# ST_LINK_V2-1.net
KiCad netlist of a schematic drawn in Altium Designer
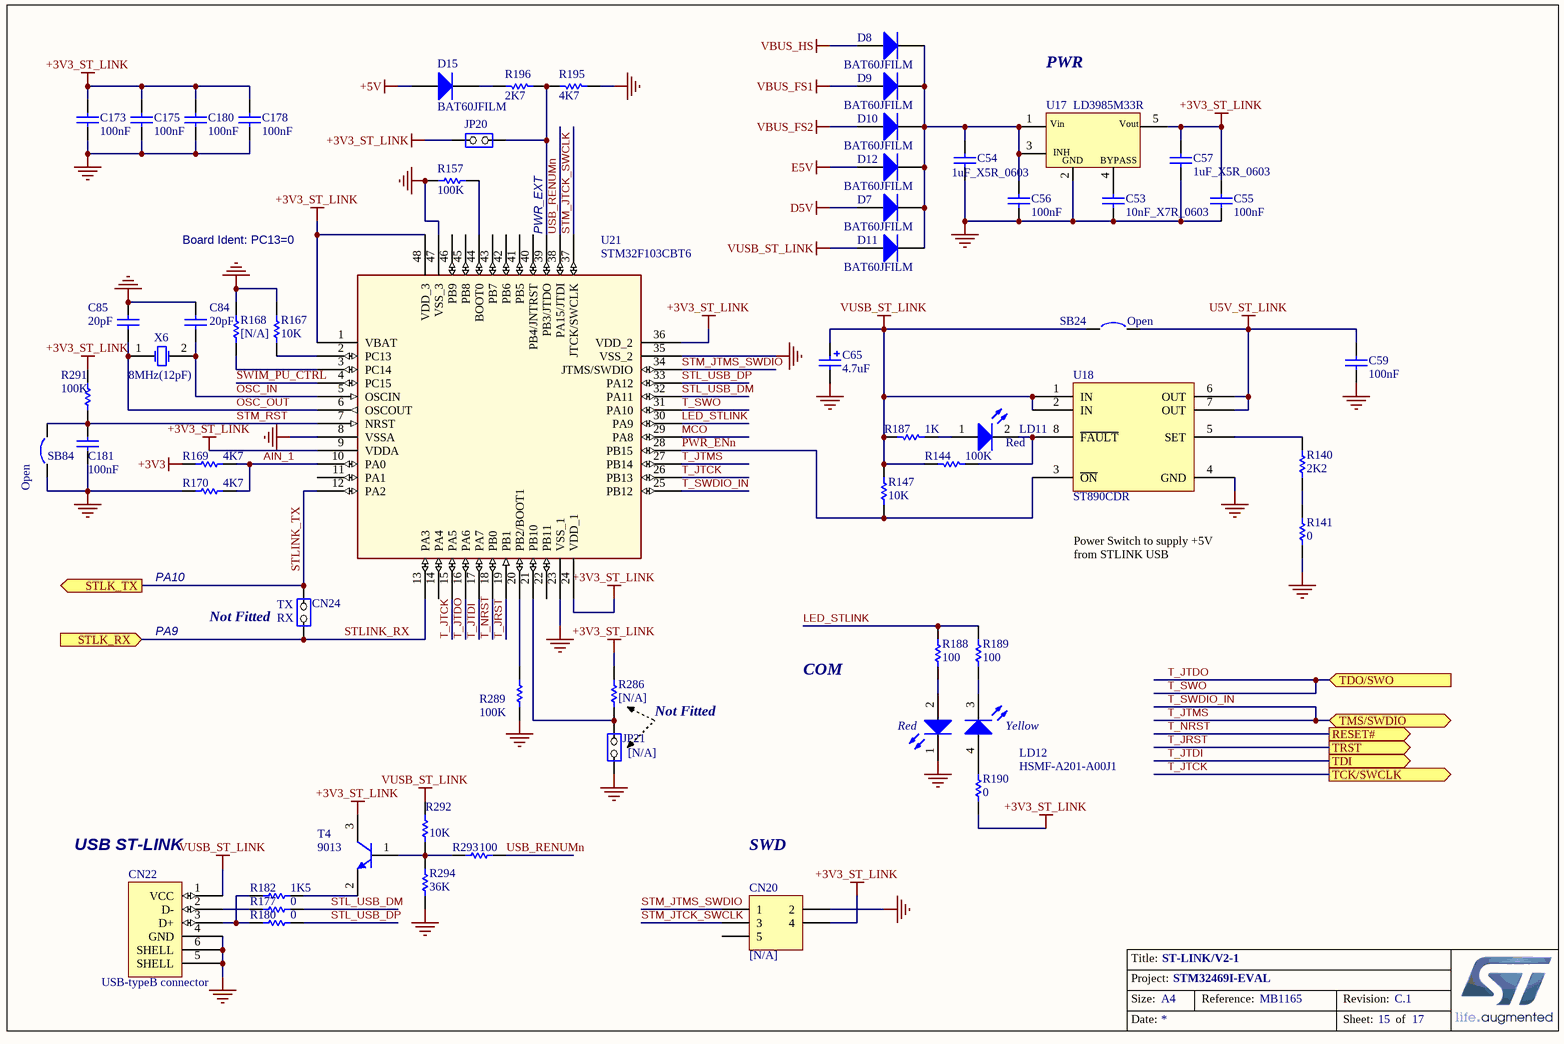
[diagram p0: ST_LINK_V2-1.SCHDOC]

(export (version "E")
  (design (tool "Eeschema 10.0.6"))
  (components
    (comp (ref "C53")
      (value "10nF_X7R_0603")
      (footprint "0603C")
      (description "0603  X7R 10NF")
      (fields (field (name "TOLERANCE") "10%"))
      (libsource (lib "MB963_1") (part "CAP SMD 0603  X7R 10000PF 50V 10%"))
    )
    (comp (ref "C54")
      (value "1uF_X5R_0603")
      (footprint "0603C")
      (description "0603  X5R 1µF")
      (fields (field (name "TOLERANCE") "10%"))
      (libsource (lib "MB963_1") (part "CAP SMD 0603  X5R 1µF 25V 10%"))
    )
    (comp (ref "C55")
      (value "100nF")
      (footprint "0603C")
      (description "Capacitor 0402 / 0603 / 0805")
      (libsource (lib "MCD_TOOLS") (part "Capacitor_ST"))
    )
    (comp (ref "C56")
      (value "100nF")
      (footprint "0603C")
      (description "Capacitor 0402 / 0603 / 0805")
      (libsource (lib "MCD_TOOLS") (part "Capacitor_ST"))
    )
    (comp (ref "C57")
      (value "1uF_X5R_0603")
      (footprint "0603C")
      (description "0603  X5R 1µF")
      (fields (field (name "TOLERANCE") "10%"))
      (libsource (lib "MB963_1") (part "CAP SMD 0603  X5R 1µF 25V 10%"))
    )
    (comp (ref "C59")
      (value "100nF")
      (footprint "0603C")
      (description "Capacitor 0402 / 0603 / 0805")
      (libsource (lib "MCD_TOOLS") (part "Capacitor_ST"))
    )
    (comp (ref "C65")
      (value "4.7uF")
      (footprint "TAN-A")
      (description "Polarized Capacitor (Radial)")
      (fields (field (name "PUBLISHER") "Altium Limited"))
      (libsource (lib "*") (part "Cap Pol1"))
    )
    (comp (ref "C84")
      (value "20pF")
      (footprint "0603C")
      (description "Capacitor 0402 / 0603 / 0805")
      (libsource (lib "MCD_TOOLS") (part "Capacitor_ST"))
    )
    (comp (ref "C85")
      (value "20pF")
      (footprint "0603C")
      (description "Capacitor 0402 / 0603 / 0805")
      (libsource (lib "MCD_TOOLS") (part "Capacitor_ST"))
    )
    (comp (ref "C173")
      (value "100nF")
      (footprint "0603C")
      (description "Capacitor 0402 / 0603 / 0805")
      (libsource (lib "MCD_TOOLS") (part "Capacitor_ST"))
    )
    (comp (ref "C175")
      (value "100nF")
      (footprint "0603C")
      (description "Capacitor 0402 / 0603 / 0805")
      (libsource (lib "MCD_TOOLS") (part "Capacitor_ST"))
    )
    (comp (ref "C178")
      (value "100nF")
      (footprint "0603C")
      (description "Capacitor 0402 / 0603 / 0805")
      (libsource (lib "MCD_TOOLS") (part "Capacitor_ST"))
    )
    (comp (ref "C180")
      (value "100nF")
      (footprint "0603C")
      (description "Capacitor 0402 / 0603 / 0805")
      (libsource (lib "MCD_TOOLS") (part "Capacitor_ST"))
    )
    (comp (ref "C181")
      (value "100nF")
      (footprint "0603C")
      (description "Capacitor 0402 / 0603 / 0805")
      (libsource (lib "MCD_TOOLS") (part "Capacitor_ST"))
    )
    (comp (ref "CN20")
      (value "[N/A]")
      (footprint "HDR_2X3-1_2R54-6")
      (description "Header, 3-Pin, Dual row")
      (fields (field (name "PUBLISHER") "Altium Limited"))
      (libsource (lib "Miscellaneous Connectors") (part "Header 3X2"))
    )
    (comp (ref "CN22")
      (value "USB-typeB connector")
      (footprint "USB-B")
      (libsource (lib "mb1045") (part "USB-typeB connector"))
    )
    (comp (ref "CN24") (value "~") (footprint "SIP2") (libsource (lib "MCD_TOOLS") (part "JP2")))
    (comp (ref "D7")
      (value "BAT60JFILM")
      (footprint "SOD-323")
      (libsource (lib "MCD_TOOLS") (part "BAT60JFILM"))
    )
    (comp (ref "D8")
      (value "BAT60JFILM")
      (footprint "SOD-323")
      (libsource (lib "MCD_TOOLS") (part "BAT60JFILM"))
    )
    (comp (ref "D9")
      (value "BAT60JFILM")
      (footprint "SOD-323")
      (libsource (lib "MCD_TOOLS") (part "BAT60JFILM"))
    )
    (comp (ref "D10")
      (value "BAT60JFILM")
      (footprint "SOD-323")
      (libsource (lib "MCD_TOOLS") (part "BAT60JFILM"))
    )
    (comp (ref "D11")
      (value "BAT60JFILM")
      (footprint "SOD-323")
      (libsource (lib "MCD_TOOLS") (part "BAT60JFILM"))
    )
    (comp (ref "D12")
      (value "BAT60JFILM")
      (footprint "SOD-323")
      (libsource (lib "MCD_TOOLS") (part "BAT60JFILM"))
    )
    (comp (ref "D15")
      (value "BAT60JFILM")
      (footprint "SOD-323")
      (description "Default Diode")
      (fields (field (name "PUBLISHER") "Altium Limited"))
      (libsource (lib "MB1144_1") (part "Diode"))
    )
    (comp (ref "JP20") (value "~") (footprint "SIP2") (libsource (lib "*") (part "JP2")))
    (comp (ref "JP21") (value "[N/A]") (footprint "SIP2") (libsource (lib "*") (part "JP2")))
    (comp (ref "LD11")
      (value "Red")
      (footprint "0603D")
      (description "Typical RED, GREEN, YELLOW, AMBER GaAs LED")
      (fields (field (name "PUBLISHER") "Altium Limited"))
      (libsource (lib "Miscellaneous Devices") (part "LED2"))
    )
    (comp (ref "LD12")
      (value "HSMF-A201-A00J1")
      (footprint "LED2_3528")
      (libsource (lib "MB819") (part "HSMF-A201-A00J1"))
    )
    (comp (ref "R140")
      (value "2K2")
      (footprint "0402R")
      (description "Resistor 0402 or 0603 or 0805")
      (libsource (lib "MCD_TOOLS") (part "Resistor_ST"))
    )
    (comp (ref "R141")
      (value "0")
      (footprint "0603R")
      (description "Resistor")
      (fields (field (name "PUBLISHER") "Altium Limited"))
      (libsource (lib "") (part "Res1_1"))
    )
    (comp (ref "R144")
      (value "100K")
      (footprint "0603R")
      (description "Resistor")
      (fields (field (name "PUBLISHER") "Altium Limited"))
      (libsource (lib "*") (part "Res1"))
    )
    (comp (ref "R147")
      (value "10K")
      (footprint "0402R")
      (description "Resistor 0402 or 0603 or 0805")
      (libsource (lib "MCD_TOOLS") (part "Resistor_ST"))
    )
    (comp (ref "R157")
      (value "100K")
      (footprint "0603R")
      (description "Resistor 0402 or 0603 or 0805")
      (libsource (lib "Miscellaneous Devices") (part "Res1"))
    )
    (comp (ref "R167")
      (value "10K")
      (footprint "0603R")
      (description "Resistor 0402 or 0603 or 0805")
      (libsource (lib "Miscellaneous Devices") (part "Res1"))
    )
    (comp (ref "R168")
      (value "[N/A]")
      (footprint "0603R")
      (description "Resistor 0402 or 0603 or 0805")
      (libsource (lib "Miscellaneous Devices") (part "Res1"))
    )
    (comp (ref "R169")
      (value "4K7")
      (footprint "0603R")
      (description "Resistor 0402 or 0603 or 0805")
      (libsource (lib "Miscellaneous Devices") (part "Res1"))
    )
    (comp (ref "R170")
      (value "4K7")
      (footprint "0603R")
      (description "Resistor 0402 or 0603 or 0805")
      (libsource (lib "Miscellaneous Devices") (part "Res1"))
    )
    (comp (ref "R177")
      (value "0")
      (footprint "0603R")
      (description "Resistor 0402 or 0603 or 0805")
      (libsource (lib "Miscellaneous Devices") (part "Res1"))
    )
    (comp (ref "R180")
      (value "0")
      (footprint "0603R")
      (description "Resistor 0402 or 0603 or 0805")
      (libsource (lib "Miscellaneous Devices") (part "Res1"))
    )
    (comp (ref "R182")
      (value "1K5")
      (footprint "0603R")
      (description "Resistor 0402 or 0603 or 0805")
      (libsource (lib "Miscellaneous Devices") (part "Res1"))
    )
    (comp (ref "R187")
      (value "1K")
      (footprint "0603R")
      (description "Resistor")
      (fields (field (name "PUBLISHER") "Altium Limited"))
      (libsource (lib "*") (part "Res1"))
    )
    (comp (ref "R188")
      (value "100")
      (footprint "0603R")
      (description "Resistor")
      (fields (field (name "PUBLISHER") "Altium Limited"))
      (libsource (lib "") (part "Res1_1"))
    )
    (comp (ref "R189")
      (value "100")
      (footprint "0603R")
      (description "Resistor")
      (fields (field (name "PUBLISHER") "Altium Limited"))
      (libsource (lib "") (part "Res1_1"))
    )
    (comp (ref "R190")
      (value "0")
      (footprint "0603R")
      (description "Resistor")
      (fields (field (name "PUBLISHER") "Altium Limited"))
      (libsource (lib "") (part "Res1_1"))
    )
    (comp (ref "R195")
      (value "4K7")
      (footprint "0603R")
      (description "Resistor")
      (fields (field (name "PUBLISHER") "Altium Limited"))
      (libsource (lib "") (part "Res1_2"))
    )
    (comp (ref "R196")
      (value "2K7")
      (footprint "0603R")
      (description "Resistor")
      (fields (field (name "PUBLISHER") "Altium Limited"))
      (libsource (lib "") (part "Res1_2"))
    )
    (comp (ref "R286")
      (value "[N/A]")
      (footprint "0603R")
      (description "Resistor")
      (fields (field (name "PUBLISHER") "Altium Limited"))
      (libsource (lib "") (part "Res1_1"))
    )
    (comp (ref "R289")
      (value "100K")
      (footprint "0603R")
      (description "Resistor 0402 or 0603 or 0805")
      (libsource (lib "Miscellaneous Devices") (part "Res1"))
    )
    (comp (ref "R291")
      (value "100K")
      (footprint "0603R")
      (description "Resistor 0402 or 0603 or 0805")
      (libsource (lib "Miscellaneous Devices") (part "Res1"))
    )
    (comp (ref "R292")
      (value "10K")
      (footprint "0603R")
      (description "Resistor")
      (fields (field (name "PUBLISHER") "Altium Limited"))
      (libsource (lib "") (part "Res1_1"))
    )
    (comp (ref "R293")
      (value "100")
      (footprint "0603R")
      (description "Resistor 0402 or 0603 or 0805")
      (libsource (lib "Miscellaneous Devices") (part "Res1"))
    )
    (comp (ref "R294")
      (value "36K")
      (footprint "0603R")
      (description "Resistor")
      (fields (field (name "PUBLISHER") "Altium Limited"))
      (libsource (lib "") (part "Res1_1"))
    )
    (comp (ref "SB24")
      (value "Open")
      (footprint "SB_0603")
      (description "Circuit Breaker")
      (fields (field (name "PUBLISHER") "Altium Limited"))
      (libsource (lib "MB1165") (part "Circuit Breaker"))
    )
    (comp (ref "SB84")
      (value "Open")
      (footprint "SB_0603")
      (description "Circuit Breaker")
      (fields (field (name "PUBLISHER") "Altium Limited"))
      (libsource (lib "MB1165") (part "Circuit Breaker"))
    )
    (comp (ref "T4")
      (value "9013")
      (footprint "SOT-23")
      (description "NPN Bipolar Transistor")
      (fields (field (name "PUBLISHER") "Altium Limited"))
      (libsource (lib "MB1167") (part "NPN"))
    )
    (comp (ref "U17")
      (value "LD3985M33R")
      (footprint "SOT23-5")
      (description "Ultra low drop-low noise BiCMOS voltage, regulators low ESR capacitors compatible")
      (libsource (lib "MCD_TOOLS") (part "LD3985M33R"))
    )
    (comp (ref "U18")
      (value "ST890CDR")
      (footprint "SOIC8_1R27_4R9X6")
      (libsource (lib "MB1167") (part "ST890CDR"))
    )
    (comp (ref "U21")
      (value "STM32F103CBT6")
      (footprint "LQFP48_0R5_9X9")
      (description "Medium-density performance line ARM-based 32-bit MCU with 64KB Flash")
      (libsource (lib "Nucleo_64") (part "STM32F103CBT6"))
    )
    (comp (ref "X6")
      (value "8MHz(12pF)")
      (footprint "XTAL_2SM_12R7X4R7")
      (description "Crystal Oscillator")
      (fields (field (name "PUBLISHER") "Altium Limited"))
      (libsource (lib "MB963_1") (part "XTAL"))
    )
  )
  (nets
    (net (code "1") (name "+3V3") (class "Default")
      (node (ref "R169") (pin "1") (pinfunction "1_1") (pintype "passive"))
    )
    (net (code "2") (name "+3V3_ST_LINK") (class "Default")
      (node (ref "C173") (pin "2") (pinfunction "2_2") (pintype "passive"))
      (node (ref "C175") (pin "2") (pinfunction "2_2") (pintype "passive"))
      (node (ref "C178") (pin "2") (pinfunction "2_2") (pintype "passive"))
      (node (ref "C180") (pin "2") (pinfunction "2_2") (pintype "passive"))
      (node (ref "C55") (pin "2") (pinfunction "2_2") (pintype "passive"))
      (node (ref "C57") (pin "1") (pinfunction "1_1") (pintype "passive"))
      (node (ref "CN20") (pin "4") (pinfunction "4_4") (pintype "passive"))
      (node (ref "JP20") (pin "1") (pinfunction "COMMON_1") (pintype "passive"))
      (node (ref "R190") (pin "2") (pinfunction "2_2") (pintype "passive"))
      (node (ref "R286") (pin "1") (pinfunction "1_1") (pintype "passive"))
      (node (ref "R291") (pin "2") (pinfunction "2_2") (pintype "passive"))
      (node (ref "T4") (pin "3") (pinfunction "C_3") (pintype "passive"))
      (node (ref "U17") (pin "5") (pinfunction "Vout_5") (pintype "passive"))
      (node (ref "U21") (pin "1") (pinfunction "VBAT_1") (pintype "power_in"))
      (node (ref "U21") (pin "24") (pinfunction "VDD_1_24") (pintype "power_in"))
      (node (ref "U21") (pin "36") (pinfunction "VDD_2_36") (pintype "power_in"))
      (node (ref "U21") (pin "48") (pinfunction "VDD_3_48") (pintype "power_in"))
      (node (ref "U21") (pin "9") (pinfunction "VDDA_9") (pintype "power_in"))
    )
    (net (code "3") (name "+5V") (class "Default")
      (node (ref "D15") (pin "1") (pinfunction "A_1") (pintype "passive"))
    )
    (net (code "4") (name "/AIN_1") (class "Default")
      (node (ref "R169") (pin "2") (pinfunction "2_2") (pintype "passive"))
      (node (ref "R170") (pin "2") (pinfunction "2_2") (pintype "passive"))
      (node (ref "U21") (pin "10") (pinfunction "PA0_10") (pintype "bidirectional"))
    )
    (net (code "5") (name "/LED_STLINK") (class "Default")
      (node (ref "R188") (pin "1") (pinfunction "1_1") (pintype "passive"))
      (node (ref "R189") (pin "1") (pinfunction "1_1") (pintype "passive"))
      (node (ref "U21") (pin "30") (pinfunction "PA9_30") (pintype "bidirectional"))
    )
    (net (code "6") (name "/MCO") (class "Default")
      (node (ref "U21") (pin "29") (pinfunction "PA8_29") (pintype "bidirectional"))
    )
    (net (code "7") (name "/OSC_IN") (class "Default")
      (node (ref "C84") (pin "1") (pinfunction "1_1") (pintype "passive"))
      (node (ref "U21") (pin "5") (pinfunction "OSCIN_5") (pintype "input"))
      (node (ref "X6") (pin "2") (pinfunction "OSC2_2") (pintype "passive"))
    )
    (net (code "8") (name "/OSC_OUT") (class "Default")
      (node (ref "C85") (pin "1") (pinfunction "1_1") (pintype "passive"))
      (node (ref "U21") (pin "6") (pinfunction "OSCOUT_6") (pintype "output"))
      (node (ref "X6") (pin "1") (pinfunction "OSC1_1") (pintype "passive"))
    )
    (net (code "9") (name "/PWR_ENn") (class "Default")
      (node (ref "R147") (pin "2") (pinfunction "2_2") (pintype "passive"))
      (node (ref "U18") (pin "3") (pinfunction "~{ON}_3") (pintype "passive"))
      (node (ref "U21") (pin "28") (pinfunction "PB15_28") (pintype "bidirectional"))
    )
    (net (code "10") (name "/STLINK_RX") (class "Default")
      (node (ref "CN24") (pin "1") (pinfunction "COMMON_1") (pintype "passive"))
      (node (ref "U21") (pin "13") (pinfunction "PA3_13") (pintype "bidirectional"))
    )
    (net (code "11") (name "/STLINK_TX") (class "Default")
      (node (ref "CN24") (pin "2") (pinfunction "NO_2") (pintype "passive"))
      (node (ref "U21") (pin "12") (pinfunction "PA2_12") (pintype "bidirectional"))
    )
    (net (code "12") (name "/STL_USB_DM") (class "Default")
      (node (ref "R177") (pin "2") (pinfunction "2_2") (pintype "passive"))
      (node (ref "U21") (pin "32") (pinfunction "PA11_32") (pintype "bidirectional"))
    )
    (net (code "13") (name "/STL_USB_DP") (class "Default")
      (node (ref "R180") (pin "2") (pinfunction "2_2") (pintype "passive"))
      (node (ref "U21") (pin "33") (pinfunction "PA12_33") (pintype "bidirectional"))
    )
    (net (code "14") (name "/STM_JTCK_SWCLK") (class "Default")
      (node (ref "CN20") (pin "3") (pinfunction "3_3") (pintype "passive"))
      (node (ref "U21") (pin "37") (pinfunction "JTCK/SWCLK_37") (pintype "bidirectional"))
    )
    (net (code "15") (name "/STM_JTMS_SWDIO") (class "Default")
      (node (ref "CN20") (pin "1") (pinfunction "1_1") (pintype "passive"))
      (node (ref "U21") (pin "34") (pinfunction "JTMS/SWDIO_34") (pintype "bidirectional"))
    )
    (net (code "16") (name "/STM_RST") (class "Default")
      (node (ref "C181") (pin "2") (pinfunction "2_2") (pintype "passive"))
      (node (ref "R291") (pin "1") (pinfunction "1_1") (pintype "passive"))
      (node (ref "SB84") (pin "2") (pinfunction "2_2") (pintype "passive"))
      (node (ref "U21") (pin "7") (pinfunction "NRST_7") (pintype "input"))
    )
    (net (code "17") (name "/SWIM_PU_CTRL") (class "Default")
      (node (ref "U21") (pin "4") (pinfunction "PC15_4") (pintype "bidirectional"))
    )
    (net (code "18") (name "/T_JRST") (class "Default")
      (node (ref "U21") (pin "19") (pinfunction "PB1_19") (pintype "input"))
    )
    (net (code "19") (name "/T_JTCK") (class "Default")
      (node (ref "U21") (pin "15") (pinfunction "PA5_15") (pintype "bidirectional"))
      (node (ref "U21") (pin "26") (pinfunction "PB13_26") (pintype "bidirectional"))
    )
    (net (code "20") (name "/T_JTDI") (class "Default")
      (node (ref "U21") (pin "17") (pinfunction "PA7_17") (pintype "bidirectional"))
    )
    (net (code "21") (name "/T_JTDO") (class "Default")
      (node (ref "U21") (pin "16") (pinfunction "PA6_16") (pintype "bidirectional"))
      (node (ref "U21") (pin "31") (pinfunction "PA10_31") (pintype "bidirectional"))
    )
    (net (code "22") (name "/T_JTMS") (class "Default")
      (node (ref "U21") (pin "25") (pinfunction "PB12_25") (pintype "bidirectional"))
      (node (ref "U21") (pin "27") (pinfunction "PB14_27") (pintype "bidirectional"))
    )
    (net (code "23") (name "/T_NRST") (class "Default")
      (node (ref "U21") (pin "18") (pinfunction "PB0_18") (pintype "bidirectional"))
    )
    (net (code "24") (name "/USB_RENUMn") (class "Default")
      (node (ref "R293") (pin "2") (pinfunction "2_2") (pintype "passive"))
      (node (ref "U21") (pin "38") (pinfunction "PA15/JTDI_38") (pintype "bidirectional"))
    )
    (net (code "25") (name "D5V") (class "Default")
      (node (ref "D7") (pin "1") (pinfunction "A_1") (pintype "passive"))
    )
    (net (code "26") (name "E5V") (class "Default")
      (node (ref "D12") (pin "1") (pinfunction "A_1") (pintype "passive"))
    )
    (net (code "27") (name "GND") (class "Default")
      (node (ref "C173") (pin "1") (pinfunction "1_1") (pintype "passive"))
      (node (ref "C175") (pin "1") (pinfunction "1_1") (pintype "passive"))
      (node (ref "C178") (pin "1") (pinfunction "1_1") (pintype "passive"))
      (node (ref "C180") (pin "1") (pinfunction "1_1") (pintype "passive"))
      (node (ref "C181") (pin "1") (pinfunction "1_1") (pintype "passive"))
      (node (ref "C53") (pin "1") (pinfunction "1_1") (pintype "passive"))
      (node (ref "C54") (pin "1") (pinfunction "1_1") (pintype "passive"))
      (node (ref "C55") (pin "1") (pinfunction "1_1") (pintype "passive"))
      (node (ref "C56") (pin "1") (pinfunction "1_1") (pintype "passive"))
      (node (ref "C57") (pin "2") (pinfunction "2_2") (pintype "passive"))
      (node (ref "C59") (pin "1") (pinfunction "1_1") (pintype "passive"))
      (node (ref "C65") (pin "2") (pinfunction "2_2") (pintype "passive"))
      (node (ref "C84") (pin "2") (pinfunction "2_2") (pintype "passive"))
      (node (ref "C85") (pin "2") (pinfunction "2_2") (pintype "passive"))
      (node (ref "CN20") (pin "2") (pinfunction "2_2") (pintype "passive"))
      (node (ref "CN22") (pin "4") (pinfunction "GND_4") (pintype "passive"))
      (node (ref "CN22") (pin "5") (pinfunction "SHELL_5") (pintype "power_in"))
      (node (ref "CN22") (pin "6") (pinfunction "SHELL_6") (pintype "power_in"))
      (node (ref "JP21") (pin "1") (pinfunction "COMMON_1") (pintype "passive"))
      (node (ref "LD12") (pin "1") (pinfunction "RED_cathode_1") (pintype "passive"))
      (node (ref "R141") (pin "1") (pinfunction "1_1") (pintype "passive"))
      (node (ref "R157") (pin "1") (pinfunction "1_1") (pintype "passive"))
      (node (ref "R167") (pin "1") (pinfunction "1_1") (pintype "passive"))
      (node (ref "R168") (pin "1") (pinfunction "1_1") (pintype "passive"))
      (node (ref "R170") (pin "1") (pinfunction "1_1") (pintype "passive"))
      (node (ref "R195") (pin "2") (pinfunction "2_2") (pintype "passive"))
      (node (ref "R289") (pin "1") (pinfunction "1_1") (pintype "passive"))
      (node (ref "R294") (pin "1") (pinfunction "1_1") (pintype "passive"))
      (node (ref "SB84") (pin "1") (pinfunction "1_1") (pintype "passive"))
      (node (ref "U17") (pin "2") (pinfunction "GND_2") (pintype "passive"))
      (node (ref "U18") (pin "4") (pinfunction "GND_4") (pintype "passive"))
      (node (ref "U21") (pin "23") (pinfunction "VSS_1_23") (pintype "power_in"))
      (node (ref "U21") (pin "35") (pinfunction "VSS_2_35") (pintype "power_in"))
      (node (ref "U21") (pin "47") (pinfunction "VSS_3_47") (pintype "power_in"))
      (node (ref "U21") (pin "8") (pinfunction "VSSA_8") (pintype "power_in"))
    )
    (net (code "28") (name "Net-(CN22-D+)") (class "Default")
      (node (ref "CN22") (pin "3") (pinfunction "D+_3") (pintype "bidirectional"))
      (node (ref "R180") (pin "1") (pinfunction "1_1") (pintype "passive"))
      (node (ref "R182") (pin "1") (pinfunction "1_1") (pintype "passive"))
    )
    (net (code "29") (name "Net-(CN22-D-)") (class "Default")
      (node (ref "CN22") (pin "2") (pinfunction "D-_2") (pintype "bidirectional"))
      (node (ref "R177") (pin "1") (pinfunction "1_1") (pintype "passive"))
    )
    (net (code "30") (name "Net-(D10-K)") (class "Default")
      (node (ref "C54") (pin "2") (pinfunction "2_2") (pintype "passive"))
      (node (ref "C56") (pin "2") (pinfunction "2_2") (pintype "passive"))
      (node (ref "D10") (pin "2") (pinfunction "K_2") (pintype "passive"))
      (node (ref "D11") (pin "2") (pinfunction "K_2") (pintype "passive"))
      (node (ref "D12") (pin "2") (pinfunction "K_2") (pintype "passive"))
      (node (ref "D7") (pin "2") (pinfunction "K_2") (pintype "passive"))
      (node (ref "D8") (pin "2") (pinfunction "K_2") (pintype "passive"))
      (node (ref "D9") (pin "2") (pinfunction "K_2") (pintype "passive"))
      (node (ref "U17") (pin "1") (pinfunction "Vin_1") (pintype "passive"))
      (node (ref "U17") (pin "3") (pinfunction "CE_3") (pintype "passive"))
    )
    (net (code "31") (name "Net-(D15-K)") (class "Default")
      (node (ref "D15") (pin "2") (pinfunction "K_2") (pintype "passive"))
      (node (ref "R196") (pin "1") (pinfunction "1_1") (pintype "passive"))
    )
    (net (code "32") (name "Net-(JP20-NO)") (class "Default")
      (node (ref "JP20") (pin "2") (pinfunction "NO_2") (pintype "passive"))
      (node (ref "R195") (pin "1") (pinfunction "1_1") (pintype "passive"))
      (node (ref "R196") (pin "2") (pinfunction "2_2") (pintype "passive"))
      (node (ref "U21") (pin "39") (pinfunction "PB3/JTDO_39") (pintype "bidirectional"))
    )
    (net (code "33") (name "Net-(JP21-NO)") (class "Default")
      (node (ref "JP21") (pin "2") (pinfunction "NO_2") (pintype "passive"))
      (node (ref "R286") (pin "2") (pinfunction "2_2") (pintype "passive"))
      (node (ref "U21") (pin "21") (pinfunction "PB10_21") (pintype "bidirectional"))
    )
    (net (code "34") (name "Net-(LD11-A)") (class "Default")
      (node (ref "LD11") (pin "1") (pinfunction "A_1") (pintype "passive"))
      (node (ref "R187") (pin "2") (pinfunction "2_2") (pintype "passive"))
    )
    (net (code "35") (name "Net-(LD11-K)") (class "Default")
      (node (ref "LD11") (pin "2") (pinfunction "K_2") (pintype "passive"))
      (node (ref "R144") (pin "2") (pinfunction "2_2") (pintype "passive"))
      (node (ref "U18") (pin "8") (pinfunction "~{FAULT}_8") (pintype "passive"))
    )
    (net (code "36") (name "Net-(LD12-Red_anode)") (class "Default")
      (node (ref "LD12") (pin "2") (pinfunction "Red_anode_2") (pintype "passive"))
      (node (ref "R188") (pin "2") (pinfunction "2_2") (pintype "passive"))
    )
    (net (code "37") (name "Net-(LD12-YellowGreen_anode)") (class "Default")
      (node (ref "LD12") (pin "4") (pinfunction "YellowGreen_anode_4") (pintype "passive"))
      (node (ref "R190") (pin "1") (pinfunction "1_1") (pintype "passive"))
    )
    (net (code "38") (name "Net-(LD12-YellowGreen_cathode)") (class "Default")
      (node (ref "LD12") (pin "3") (pinfunction "YellowGreen_cathode_3") (pintype "passive"))
      (node (ref "R189") (pin "2") (pinfunction "2_2") (pintype "passive"))
    )
    (net (code "39") (name "Net-(R140-Pad1)") (class "Default")
      (node (ref "R140") (pin "1") (pinfunction "1_1") (pintype "passive"))
      (node (ref "R141") (pin "2") (pinfunction "2_2") (pintype "passive"))
    )
    (net (code "40") (name "Net-(T4-B)") (class "Default")
      (node (ref "R292") (pin "1") (pinfunction "1_1") (pintype "passive"))
      (node (ref "R293") (pin "1") (pinfunction "1_1") (pintype "passive"))
      (node (ref "R294") (pin "2") (pinfunction "2_2") (pintype "passive"))
      (node (ref "T4") (pin "1") (pinfunction "B_1") (pintype "passive"))
    )
    (net (code "41") (name "Net-(T4-E)") (class "Default")
      (node (ref "R182") (pin "2") (pinfunction "2_2") (pintype "passive"))
      (node (ref "T4") (pin "2") (pinfunction "E_2") (pintype "passive"))
    )
    (net (code "42") (name "Net-(U17-BYPASS)") (class "Default")
      (node (ref "C53") (pin "2") (pinfunction "2_2") (pintype "passive"))
      (node (ref "U17") (pin "4") (pinfunction "BYPASS_4") (pintype "passive"))
    )
    (net (code "43") (name "Net-(U18-SET)") (class "Default")
      (node (ref "R140") (pin "2") (pinfunction "2_2") (pintype "passive"))
      (node (ref "U18") (pin "5") (pinfunction "SET_5") (pintype "passive"))
    )
    (net (code "44") (name "Net-(U21-BOOT0)") (class "Default")
      (node (ref "R157") (pin "2") (pinfunction "2_2") (pintype "passive"))
      (node (ref "U21") (pin "44") (pinfunction "BOOT0_44") (pintype "bidirectional"))
    )
    (net (code "45") (name "Net-(U21-PB2{slash}BOOT1)") (class "Default")
      (node (ref "R289") (pin "2") (pinfunction "2_2") (pintype "passive"))
      (node (ref "U21") (pin "20") (pinfunction "PB2/BOOT1_20") (pintype "bidirectional"))
    )
    (net (code "46") (name "Net-(U21-PC13)") (class "Default")
      (node (ref "R167") (pin "2") (pinfunction "2_2") (pintype "passive"))
      (node (ref "U21") (pin "2") (pinfunction "PC13_2") (pintype "bidirectional"))
    )
    (net (code "47") (name "Net-(U21-PC14)") (class "Default")
      (node (ref "R168") (pin "2") (pinfunction "2_2") (pintype "passive"))
      (node (ref "U21") (pin "3") (pinfunction "PC14_3") (pintype "bidirectional"))
    )
    (net (code "48") (name "U5V_ST_LINK") (class "Default")
      (node (ref "C59") (pin "2") (pinfunction "2_2") (pintype "passive"))
      (node (ref "SB24") (pin "2") (pinfunction "2_2") (pintype "passive"))
      (node (ref "U18") (pin "6") (pinfunction "OUT_6") (pintype "passive"))
      (node (ref "U18") (pin "7") (pinfunction "OUT_7") (pintype "passive"))
    )
    (net (code "49") (name "VBUS_FS1") (class "Default")
      (node (ref "D9") (pin "1") (pinfunction "A_1") (pintype "passive"))
    )
    (net (code "50") (name "VBUS_FS2") (class "Default")
      (node (ref "D10") (pin "1") (pinfunction "A_1") (pintype "passive"))
    )
    (net (code "51") (name "VBUS_HS") (class "Default")
      (node (ref "D8") (pin "1") (pinfunction "A_1") (pintype "passive"))
    )
    (net (code "52") (name "VUSB_ST_LINK") (class "Default")
      (node (ref "C65") (pin "1") (pinfunction "1_1") (pintype "passive"))
      (node (ref "CN22") (pin "1") (pinfunction "VCC_1") (pintype "bidirectional"))
      (node (ref "D11") (pin "1") (pinfunction "A_1") (pintype "passive"))
      (node (ref "R144") (pin "1") (pinfunction "1_1") (pintype "passive"))
      (node (ref "R147") (pin "1") (pinfunction "1_1") (pintype "passive"))
      (node (ref "R187") (pin "1") (pinfunction "1_1") (pintype "passive"))
      (node (ref "R292") (pin "2") (pinfunction "2_2") (pintype "passive"))
      (node (ref "SB24") (pin "1") (pinfunction "1_1") (pintype "passive"))
      (node (ref "U18") (pin "1") (pinfunction "IN_1") (pintype "passive"))
      (node (ref "U18") (pin "2") (pinfunction "IN_2") (pintype "passive"))
    )
    (net (code "53") (name "unconnected-(CN20-Pad5)") (class "Default")
      (node (ref "CN20") (pin "5") (pinfunction "5_5") (pintype "passive"))
    )
    (net (code "54") (name "unconnected-(U21-PA1-Pad11)") (class "Default")
      (node (ref "U21") (pin "11") (pinfunction "PA1_11") (pintype "bidirectional"))
    )
    (net (code "55") (name "unconnected-(U21-PA4-Pad14)") (class "Default")
      (node (ref "U21") (pin "14") (pinfunction "PA4_14") (pintype "bidirectional"))
    )
    (net (code "56") (name "unconnected-(U21-PB4{slash}JNTRST-Pad40)") (class "Default")
      (node (ref "U21") (pin "40") (pinfunction "PB4/JNTRST_40") (pintype "bidirectional"))
    )
    (net (code "57") (name "unconnected-(U21-PB5-Pad41)") (class "Default")
      (node (ref "U21") (pin "41") (pinfunction "PB5_41") (pintype "bidirectional"))
    )
    (net (code "58") (name "unconnected-(U21-PB6-Pad42)") (class "Default")
      (node (ref "U21") (pin "42") (pinfunction "PB6_42") (pintype "bidirectional"))
    )
    (net (code "59") (name "unconnected-(U21-PB7-Pad43)") (class "Default")
      (node (ref "U21") (pin "43") (pinfunction "PB7_43") (pintype "bidirectional"))
    )
    (net (code "60") (name "unconnected-(U21-PB8-Pad45)") (class "Default")
      (node (ref "U21") (pin "45") (pinfunction "PB8_45") (pintype "bidirectional"))
    )
    (net (code "61") (name "unconnected-(U21-PB9-Pad46)") (class "Default")
      (node (ref "U21") (pin "46") (pinfunction "PB9_46") (pintype "bidirectional"))
    )
    (net (code "62") (name "unconnected-(U21-PB11-Pad22)") (class "Default")
      (node (ref "U21") (pin "22") (pinfunction "PB11_22") (pintype "bidirectional"))
    )
  )
)
